# Rev7.net
KiCad netlist of a schematic drawn in EAGLE
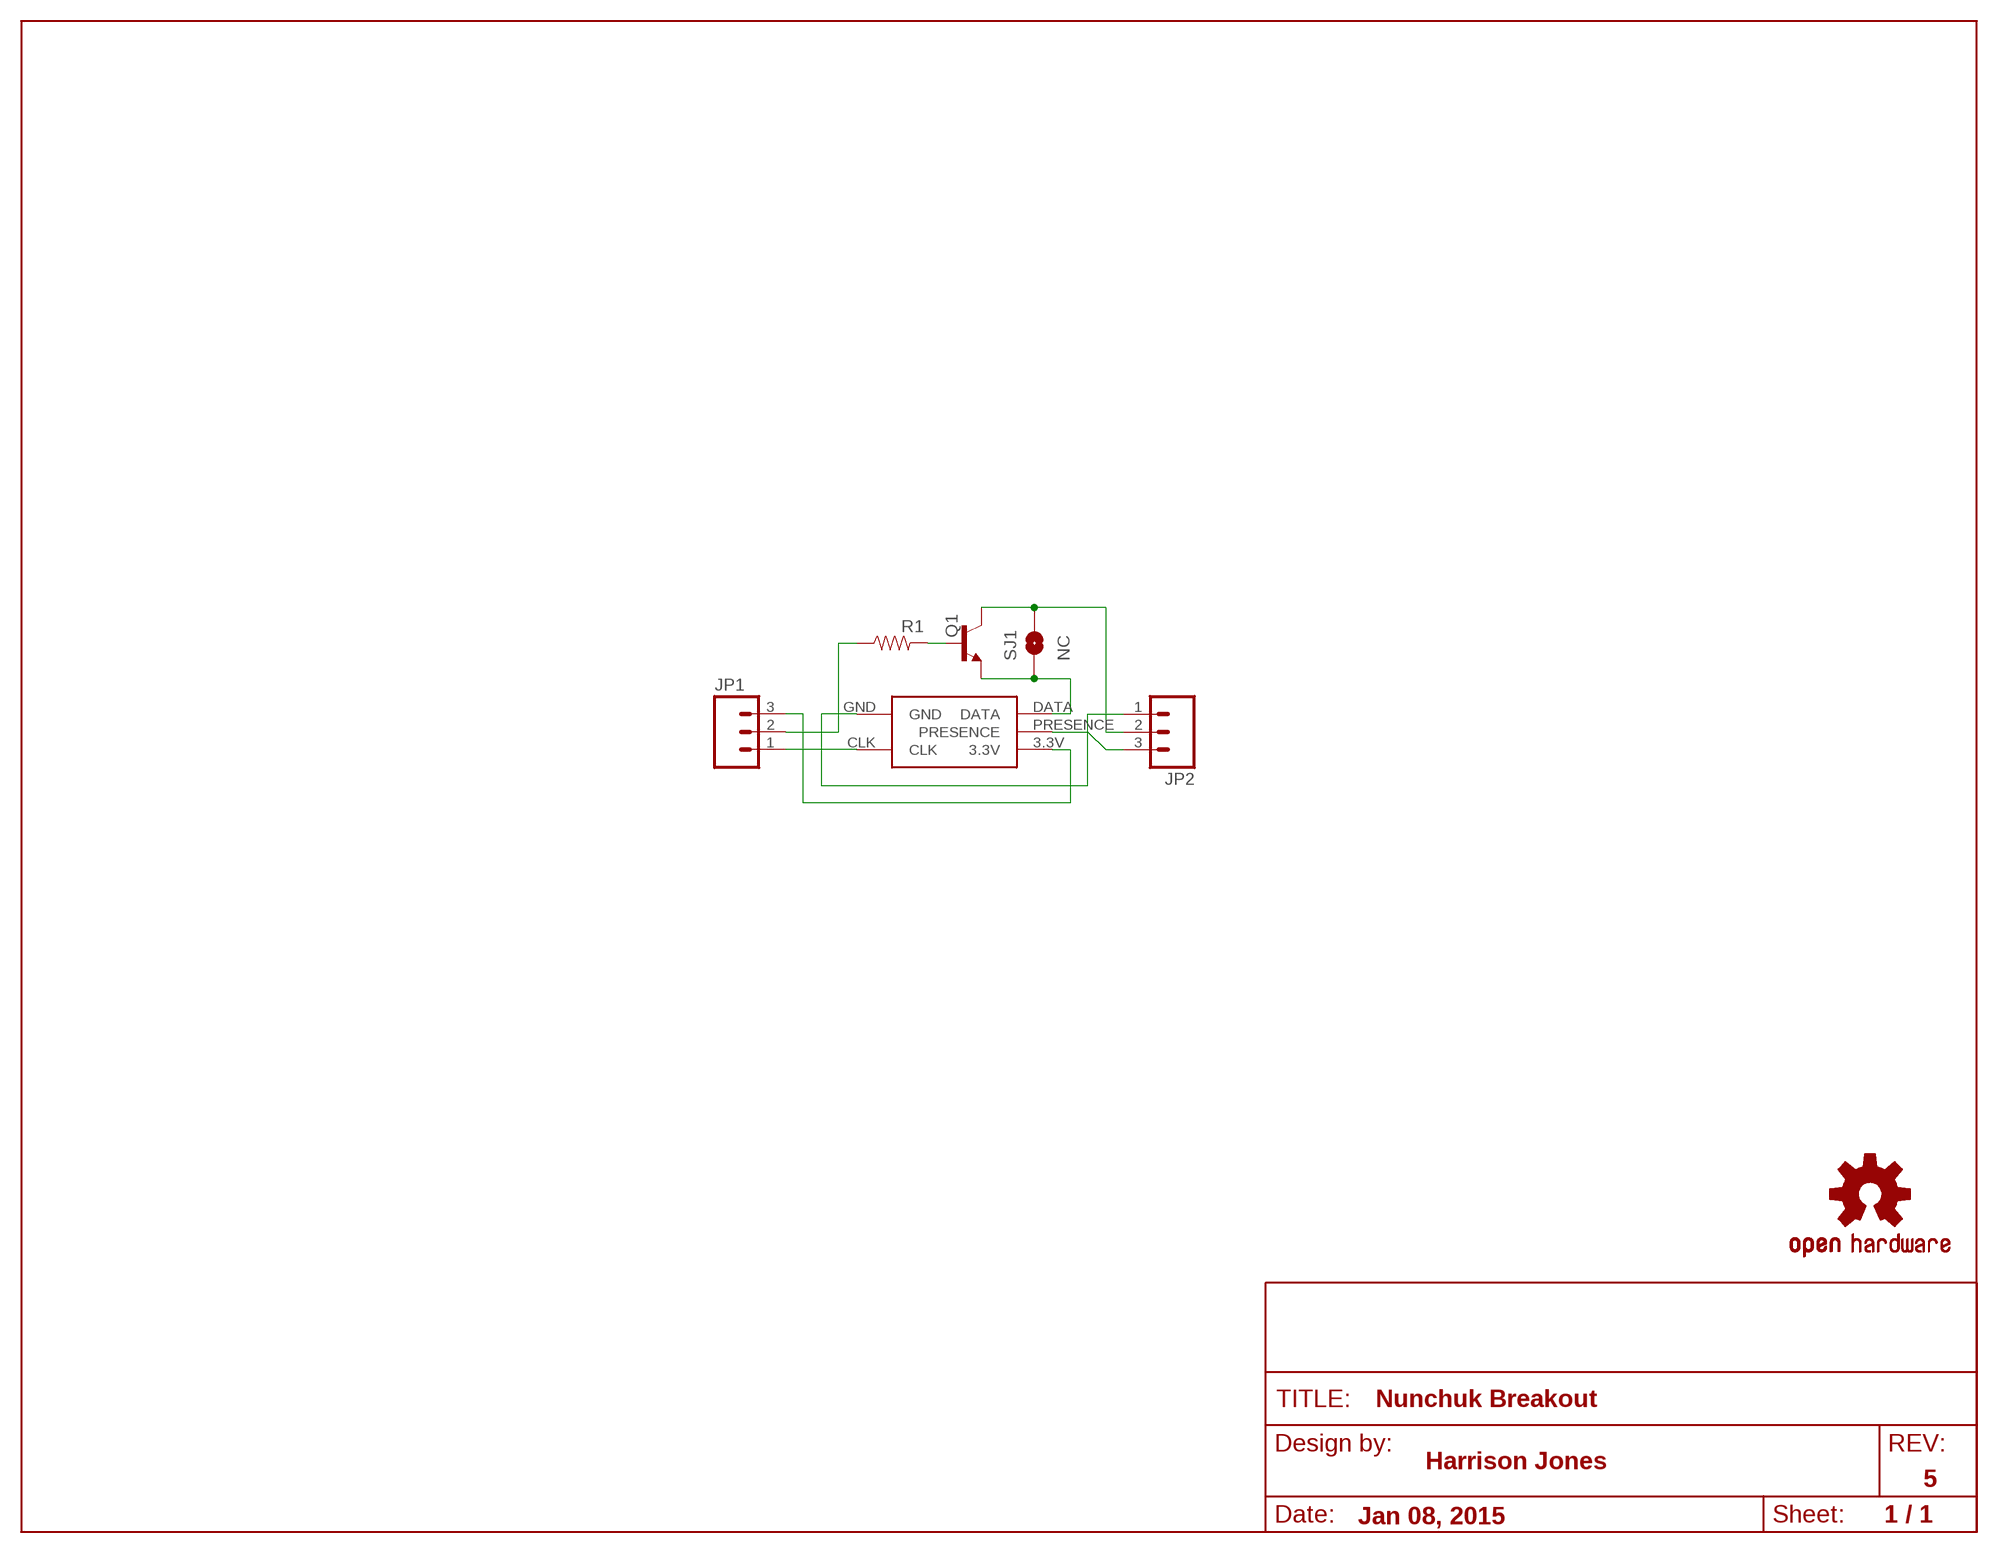
[diagram p0: schematic, sheet 1]

(export (version "E")
  (design (tool "Eeschema 10.0.6"))
  (components
    (comp (ref "JP1")
      (value "M03PTH")
      (footprint "eagle-import:1X03")
      (libsource (lib "eagle-import") (part "M03PTH"))
    )
    (comp (ref "JP2")
      (value "M03PTH")
      (footprint "eagle-import:1X03")
      (libsource (lib "eagle-import") (part "M03PTH"))
    )
    (comp (ref "LOGO1")
      (value "OSHW-LOGOS")
      (footprint "eagle-import:OSHW-LOGO-S")
      (libsource (lib "eagle-import") (part "OSHW-LOGOS"))
    )
    (comp (ref "Q1")
      (value "TRANSISTOR_NPNSOT23")
      (footprint "eagle-import:SOT23")
      (libsource (lib "eagle-import") (part "TRANSISTOR_NPNSOT23"))
    )
    (comp (ref "R1")
      (value "RESISTOR0603")
      (footprint "eagle-import:0603-RES")
      (libsource (lib "eagle-import") (part "RESISTOR0603"))
    )
    (comp (ref "SJ1")
      (value "NC")
      (footprint "eagle-import:SJ_2S-TRACE")
      (libsource (lib "eagle-import") (part "SOLDERJUMPERTRACE"))
    )
    (comp (ref "U$1")
      (value "NUNCHUCKLOCL")
      (footprint "eagle-import:NUNCHUCK-LOCK")
      (libsource (lib "eagle-import") (part "NUNCHUCKLOCL"))
    )
    (comp (ref "U$2")
      (value "DOC_FIELD")
      (footprint "eagle-import:DOC_FIELD")
      (libsource (lib "eagle-import") (part "DOC_FIELD"))
    )
  )
  (nets
    (net (code "1") (name "Net-(JP1-Pad1)") (class "Default")
      (node (ref "JP1") (pin "1") (pinfunction "1_1") (pintype "passive"))
      (node (ref "U$1") (pin "CLK") (pinfunction "CLK_CLK") (pintype "bidirectional"))
    )
    (net (code "2") (name "Net-(JP1-Pad2)") (class "Default")
      (node (ref "JP1") (pin "2") (pinfunction "2_2") (pintype "passive"))
      (node (ref "R1") (pin "1") (pinfunction "1_1") (pintype "passive"))
    )
    (net (code "3") (name "Net-(JP1-Pad3)") (class "Default")
      (node (ref "JP1") (pin "3") (pinfunction "3_3") (pintype "passive"))
      (node (ref "U$1") (pin "3.3V") (pinfunction "3.3V_3.3V") (pintype "bidirectional"))
    )
    (net (code "4") (name "Net-(JP2-Pad1)") (class "Default")
      (node (ref "JP2") (pin "1") (pinfunction "1_1") (pintype "passive"))
      (node (ref "U$1") (pin "GND") (pinfunction "GND_GND") (pintype "bidirectional"))
    )
    (net (code "5") (name "Net-(JP2-Pad3)") (class "Default")
      (node (ref "JP2") (pin "3") (pinfunction "3_3") (pintype "passive"))
      (node (ref "U$1") (pin "PRESENCE") (pinfunction "PRESENCE_PRESENCE") (pintype "bidirectional"))
    )
    (net (code "6") (name "Net-(Q1-B)") (class "Default")
      (node (ref "Q1") (pin "1") (pinfunction "B_1") (pintype "passive"))
      (node (ref "R1") (pin "2") (pinfunction "2_2") (pintype "passive"))
    )
    (net (code "7") (name "Net-(Q1-C)") (class "Default")
      (node (ref "JP2") (pin "2") (pinfunction "2_2") (pintype "passive"))
      (node (ref "Q1") (pin "3") (pinfunction "C_3") (pintype "passive"))
      (node (ref "SJ1") (pin "2") (pinfunction "2_2") (pintype "passive"))
    )
    (net (code "8") (name "Net-(Q1-E)") (class "Default")
      (node (ref "Q1") (pin "2") (pinfunction "E_2") (pintype "passive"))
      (node (ref "SJ1") (pin "1") (pinfunction "1_1") (pintype "passive"))
      (node (ref "U$1") (pin "DATA") (pinfunction "DATA_DATA") (pintype "bidirectional"))
    )
  )
)
